# DCDC_1.net
KiCad netlist of a schematic drawn in Altium Designer
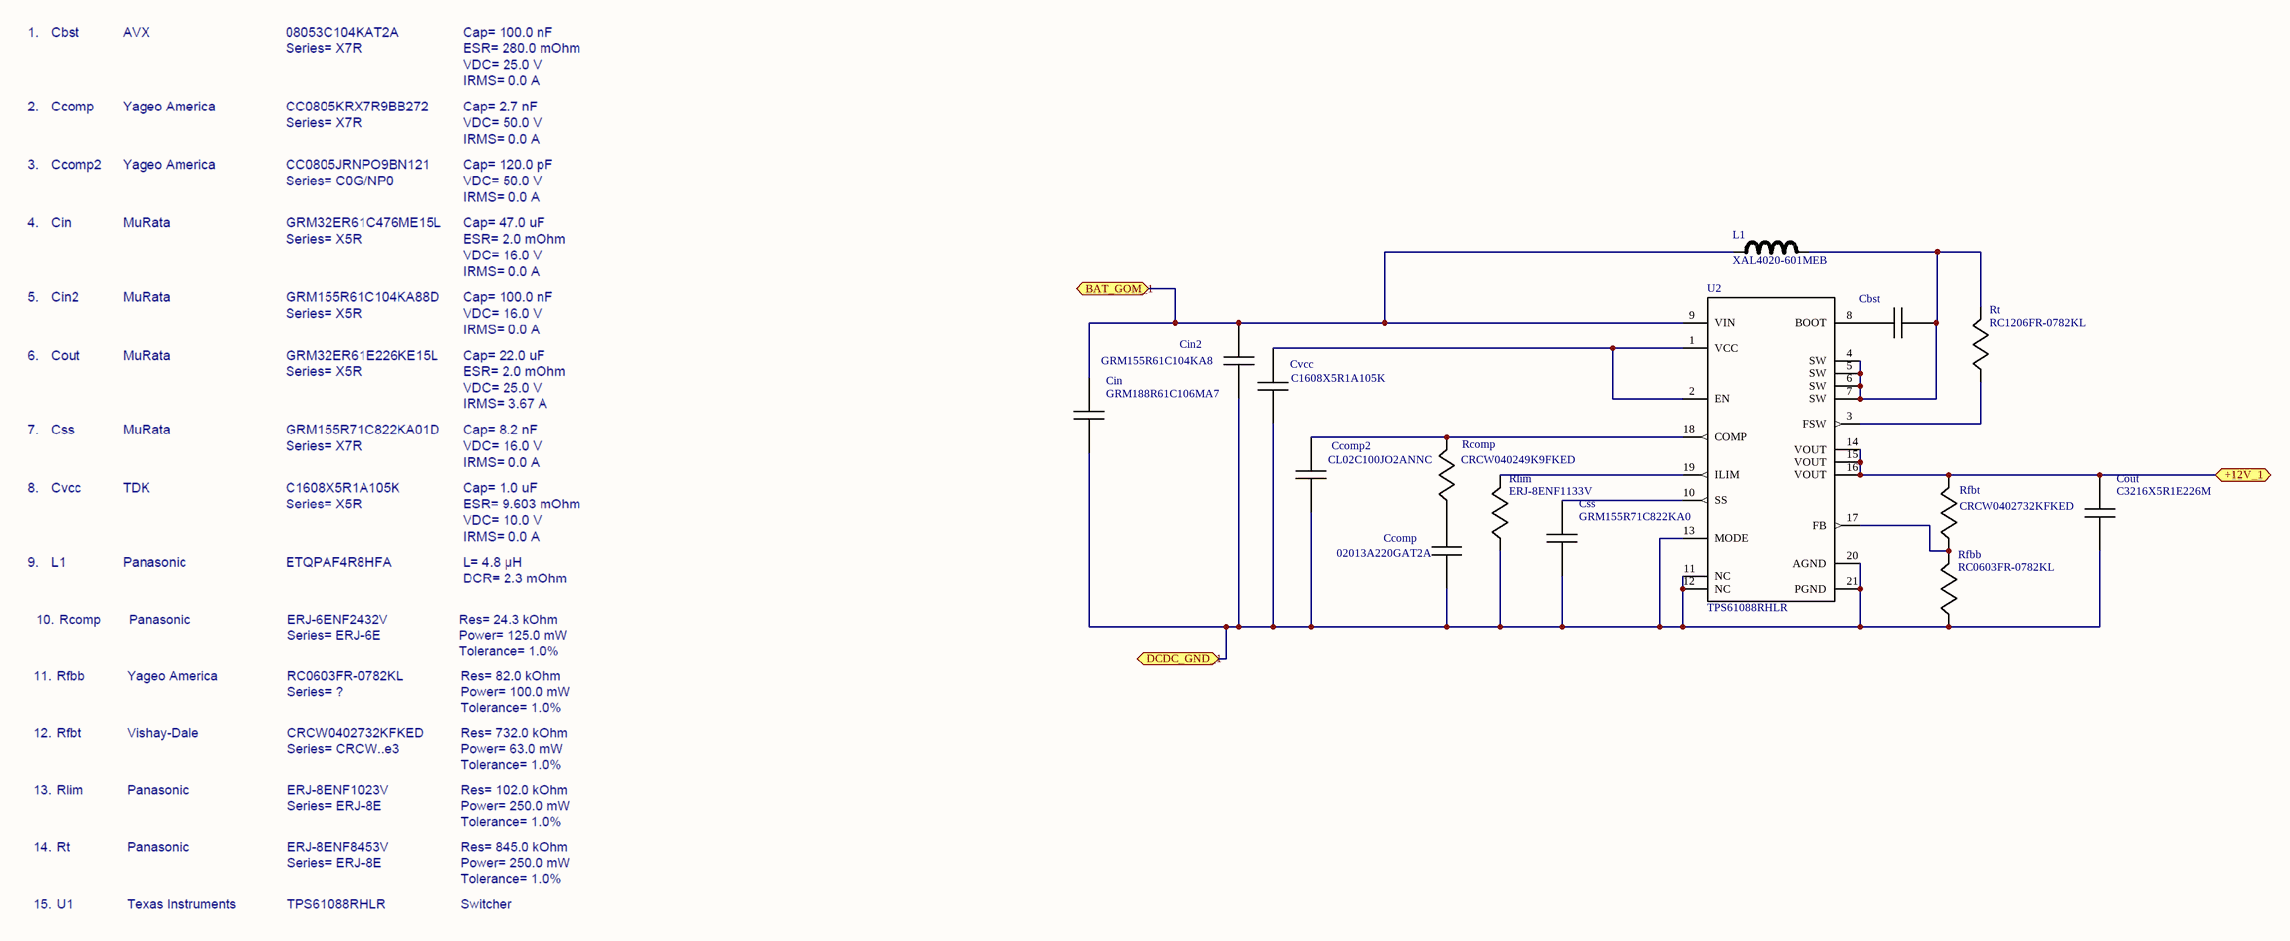
[diagram p0: DCDC_1.SchDoc]

(export (version "E")
  (design (tool "Eeschema 10.0.6"))
  (components
    (comp (ref "Cbst")
      (value "C1005X5R1A104K")
      (footprint "1005")
      (description "Imported")
      (libsource (lib "2015-10-09_12-54-35") (part "C1005X5R1A104K"))
    )
    (comp (ref "Ccomp")
      (value "02013A220GAT2A")
      (footprint "0201")
      (description "Imported")
      (libsource (lib "2015-10-09_12-54-35") (part "02013A220GAT2A"))
    )
    (comp (ref "Ccomp2")
      (value "CL02C100JO2ANNC")
      (footprint "01005")
      (description "Imported")
      (libsource (lib "2015-10-09_12-54-35") (part "CL02C100JO2ANNC"))
    )
    (comp (ref "Cin")
      (value "GRM188R61C106MA7")
      (footprint "0603")
      (description "Imported")
      (fields (field (name "MANUFACTURER_PART_NUMBER") "GRM188R61C106MA73D"))
      (libsource (lib "2015-10-09_12-54-35") (part "GRM188R61C106MA7"))
    )
    (comp (ref "Cin2")
      (value "GRM155R61C104KA8")
      (footprint "0402")
      (description "Imported")
      (fields (field (name "MANUFACTURER_PART_NUMBER") "GRM155R61C104KA88D"))
      (libsource (lib "2015-10-09_12-54-35") (part "GRM155R61C104KA8"))
    )
    (comp (ref "Cout")
      (value "C3216X5R1E226M")
      (footprint "1206")
      (description "Imported")
      (libsource (lib "2015-10-09_12-54-35") (part "C3216X5R1E226M"))
    )
    (comp (ref "Css")
      (value "GRM155R71C822KA0")
      (footprint "0402")
      (description "Imported")
      (fields (field (name "MANUFACTURER_PART_NUMBER") "GRM155R71C822KA01D"))
      (libsource (lib "2015-10-09_12-54-35") (part "GRM155R71C822KA0"))
    )
    (comp (ref "Cvcc")
      (value "C1608X5R1A105K")
      (footprint "1608")
      (description "Imported")
      (libsource (lib "2015-10-09_12-54-35") (part "C1608X5R1A105K"))
    )
    (comp (ref "L1")
      (value "XAL4020-601MEB")
      (footprint "XAL4020")
      (description "Imported")
      (libsource (lib "2015-10-09_12-54-35") (part "XAL4020-601MEB"))
    )
    (comp (ref "Rcomp")
      (value "CRCW040249K9FKED")
      (footprint "0402")
      (description "Imported")
      (libsource (lib "2015-10-09_12-54-35") (part "CRCW040249K9FKED"))
    )
    (comp (ref "Rfbb")
      (value "RC0603FR-0782KL")
      (footprint "0603")
      (description "Imported")
      (libsource (lib "2015-10-09_12-54-35") (part "RC0603FR-0782KL"))
    )
    (comp (ref "Rfbt")
      (value "CRCW0402732KFKED")
      (footprint "0402")
      (description "Imported")
      (libsource (lib "2015-10-09_12-54-35") (part "CRCW0402732KFKED"))
    )
    (comp (ref "Rlim")
      (value "ERJ-8ENF1133V")
      (footprint "1206")
      (description "Imported")
      (libsource (lib "2015-10-09_12-54-35") (part "ERJ-8ENF1133V"))
    )
    (comp (ref "Rt")
      (value "RC1206FR-0782KL")
      (footprint "1206")
      (description "Imported")
      (libsource (lib "2015-10-09_12-54-35") (part "RC1206FR-0782KL"))
    )
    (comp (ref "U2")
      (value "TPS61088RHLR")
      (footprint "RHL0020A")
      (description "Imported")
      (fields
        (field (name "ALTERNATE PARTNUMBER") "TPS61088RHLT")
        (field (name "MANUFACTURER") "Texas Instruments")
      )
      (libsource (lib "2015-10-09_12-53-27") (part "TPS61088RHLR"))
    )
  )
  (nets
    (net (code "1") (name "/+12V_1") (class "Default")
      (node (ref "Cout") (pin "1") (pinfunction "1_1") (pintype "passive"))
      (node (ref "Rfbt") (pin "1") (pinfunction "1_1") (pintype "passive"))
      (node (ref "U2") (pin "14") (pinfunction "VOUT_14") (pintype "passive"))
      (node (ref "U2") (pin "15") (pinfunction "VOUT_15") (pintype "passive"))
      (node (ref "U2") (pin "16") (pinfunction "VOUT_16") (pintype "passive"))
    )
    (net (code "2") (name "/BAT_GOM_1") (class "Default")
      (node (ref "Cin") (pin "1") (pinfunction "1_1") (pintype "passive"))
      (node (ref "Cin2") (pin "1") (pinfunction "1_1") (pintype "passive"))
      (node (ref "L1") (pin "1") (pinfunction "1_1") (pintype "passive"))
      (node (ref "U2") (pin "9") (pinfunction "VIN_9") (pintype "passive"))
    )
    (net (code "3") (name "/DCDC_GND_1") (class "Default")
      (node (ref "Ccomp") (pin "2") (pinfunction "2_2") (pintype "passive"))
      (node (ref "Ccomp2") (pin "1") (pinfunction "1_1") (pintype "passive"))
      (node (ref "Cin") (pin "2") (pinfunction "2_2") (pintype "passive"))
      (node (ref "Cin2") (pin "2") (pinfunction "2_2") (pintype "passive"))
      (node (ref "Cout") (pin "2") (pinfunction "2_2") (pintype "passive"))
      (node (ref "Css") (pin "1") (pinfunction "1_1") (pintype "passive"))
      (node (ref "Cvcc") (pin "1") (pinfunction "1_1") (pintype "passive"))
      (node (ref "Rfbb") (pin "2") (pinfunction "2_2") (pintype "passive"))
      (node (ref "Rlim") (pin "2") (pinfunction "2_2") (pintype "passive"))
      (node (ref "U2") (pin "11") (pinfunction "NC_11") (pintype "passive"))
      (node (ref "U2") (pin "12") (pinfunction "NC_12") (pintype "passive"))
      (node (ref "U2") (pin "13") (pinfunction "MODE_13") (pintype "passive"))
      (node (ref "U2") (pin "20") (pinfunction "AGND_20") (pintype "passive"))
      (node (ref "U2") (pin "21") (pinfunction "PGND_21") (pintype "passive"))
    )
    (net (code "4") (name "Net-(Cbst-Pad1)") (class "Default")
      (node (ref "Cbst") (pin "1") (pinfunction "1_1") (pintype "passive"))
      (node (ref "L1") (pin "2") (pinfunction "2_2") (pintype "passive"))
      (node (ref "Rt") (pin "1") (pinfunction "1_1") (pintype "passive"))
      (node (ref "U2") (pin "4") (pinfunction "SW_4") (pintype "power_in"))
      (node (ref "U2") (pin "5") (pinfunction "SW_5") (pintype "power_in"))
      (node (ref "U2") (pin "6") (pinfunction "SW_6") (pintype "power_in"))
      (node (ref "U2") (pin "7") (pinfunction "SW_7") (pintype "power_in"))
    )
    (net (code "5") (name "Net-(Ccomp-Pad1)") (class "Default")
      (node (ref "Ccomp") (pin "1") (pinfunction "1_1") (pintype "passive"))
      (node (ref "Rcomp") (pin "2") (pinfunction "2_2") (pintype "passive"))
    )
    (net (code "6") (name "Net-(U2-BOOT)") (class "Default")
      (node (ref "Cbst") (pin "2") (pinfunction "2_2") (pintype "passive"))
      (node (ref "U2") (pin "8") (pinfunction "BOOT_8") (pintype "power_in"))
    )
    (net (code "7") (name "Net-(U2-COMP)") (class "Default")
      (node (ref "Ccomp2") (pin "2") (pinfunction "2_2") (pintype "passive"))
      (node (ref "Rcomp") (pin "1") (pinfunction "1_1") (pintype "passive"))
      (node (ref "U2") (pin "18") (pinfunction "COMP_18") (pintype "output"))
    )
    (net (code "8") (name "Net-(U2-EN)") (class "Default")
      (node (ref "Cvcc") (pin "2") (pinfunction "2_2") (pintype "passive"))
      (node (ref "U2") (pin "1") (pinfunction "VCC_1") (pintype "passive"))
      (node (ref "U2") (pin "2") (pinfunction "EN_2") (pintype "passive"))
    )
    (net (code "9") (name "Net-(U2-FB)") (class "Default")
      (node (ref "Rfbb") (pin "1") (pinfunction "1_1") (pintype "passive"))
      (node (ref "Rfbt") (pin "2") (pinfunction "2_2") (pintype "passive"))
      (node (ref "U2") (pin "17") (pinfunction "FB_17") (pintype "output"))
    )
    (net (code "10") (name "Net-(U2-FSW)") (class "Default")
      (node (ref "Rt") (pin "2") (pinfunction "2_2") (pintype "passive"))
      (node (ref "U2") (pin "3") (pinfunction "FSW_3") (pintype "output"))
    )
    (net (code "11") (name "Net-(U2-ILIM)") (class "Default")
      (node (ref "Rlim") (pin "1") (pinfunction "1_1") (pintype "passive"))
      (node (ref "U2") (pin "19") (pinfunction "ILIM_19") (pintype "output"))
    )
    (net (code "12") (name "Net-(U2-SS)") (class "Default")
      (node (ref "Css") (pin "2") (pinfunction "2_2") (pintype "passive"))
      (node (ref "U2") (pin "10") (pinfunction "SS_10") (pintype "output"))
    )
  )
)
